# Sheet1.net
KiCad netlist of a schematic drawn in Altium Designer
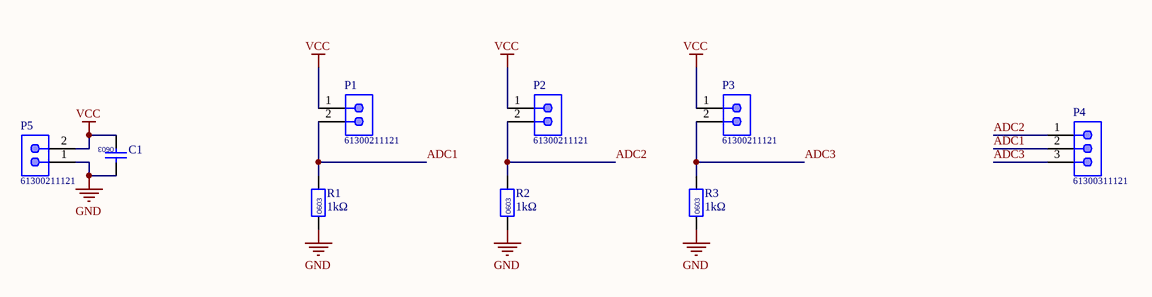
[diagram p0: Sheet1.SchDoc]

(export (version "E")
  (design (tool "Eeschema 10.0.6"))
  (components
    (comp (ref "C1")
      (value "~")
      (footprint "C_0603")
      (description "MLCC - SMD/SMT Capacitor 50V")
      (fields (field (name "VOLTAGE") "50V"))
      (libsource (lib "2021-1") (part "Capacitor_0603"))
    )
    (comp (ref "P1")
      (value "61300211121")
      (footprint "61300211121")
      (description "WR-PHD Pin Header, THT, pitch 2.54mm, Single Row, Vertical, 2p")
      (fields (field (name "MANUFACTURER") "Wurth Elektronik"))
      (libsource (lib "Gold_Pin_WE_2_54(rev20a)") (part "61300211121"))
    )
    (comp (ref "P2")
      (value "61300211121")
      (footprint "61300211121")
      (description "WR-PHD Pin Header, THT, pitch 2.54mm, Single Row, Vertical, 2p")
      (fields (field (name "MANUFACTURER") "Wurth Elektronik"))
      (libsource (lib "Gold_Pin_WE_2_54(rev20a)") (part "61300211121"))
    )
    (comp (ref "P3")
      (value "61300211121")
      (footprint "61300211121")
      (description "WR-PHD Pin Header, THT, pitch 2.54mm, Single Row, Vertical, 2p")
      (fields (field (name "MANUFACTURER") "Wurth Elektronik"))
      (libsource (lib "Gold_Pin_WE_2_54(rev20a)") (part "61300211121"))
    )
    (comp (ref "P4")
      (value "61300311121")
      (footprint "61300311121")
      (description "WR-PHD Pin Header, THT, pitch 2.54mm, Single Row, Vertical, 3p")
      (fields (field (name "MANUFACTURER") "Wurth Elektronik"))
      (libsource (lib "Gold_Pin_WE_2_54(rev20a)") (part "61300311121"))
    )
    (comp (ref "P5")
      (value "61300211121")
      (footprint "61300211121")
      (description "WR-PHD Pin Header, THT, pitch 2.54mm, Single Row, Vertical, 2p")
      (fields (field (name "MANUFACTURER") "Wurth Elektronik"))
      (libsource (lib "Gold_Pin_WE_2_54(rev20a)") (part "61300211121"))
    )
    (comp (ref "R1")
      (value "1kΩ")
      (footprint "R_0603")
      (description "SMT Resistor")
      (libsource (lib "2021-1") (part "Resistor_0603"))
    )
    (comp (ref "R2")
      (value "1kΩ")
      (footprint "R_0603")
      (description "SMT Resistor")
      (libsource (lib "2021-1") (part "Resistor_0603"))
    )
    (comp (ref "R3")
      (value "1kΩ")
      (footprint "R_0603")
      (description "SMT Resistor")
      (libsource (lib "2021-1") (part "Resistor_0603"))
    )
  )
  (nets
    (net (code "1") (name "/ADC1") (class "Default")
      (node (ref "P1") (pin "2") (pinfunction "2_2") (pintype "passive"))
      (node (ref "P4") (pin "2") (pinfunction "2_2") (pintype "passive"))
      (node (ref "R1") (pin "2") (pinfunction "2_2") (pintype "passive"))
    )
    (net (code "2") (name "/ADC2") (class "Default")
      (node (ref "P2") (pin "2") (pinfunction "2_2") (pintype "passive"))
      (node (ref "P4") (pin "1") (pinfunction "1_1") (pintype "passive"))
      (node (ref "R2") (pin "2") (pinfunction "2_2") (pintype "passive"))
    )
    (net (code "3") (name "/ADC3") (class "Default")
      (node (ref "P3") (pin "2") (pinfunction "2_2") (pintype "passive"))
      (node (ref "P4") (pin "3") (pinfunction "3_3") (pintype "passive"))
      (node (ref "R3") (pin "2") (pinfunction "2_2") (pintype "passive"))
    )
    (net (code "4") (name "GND") (class "Default")
      (node (ref "C1") (pin "2") (pinfunction "2_2") (pintype "passive"))
      (node (ref "P5") (pin "1") (pinfunction "1_1") (pintype "passive"))
      (node (ref "R1") (pin "1") (pinfunction "1_1") (pintype "passive"))
      (node (ref "R2") (pin "1") (pinfunction "1_1") (pintype "passive"))
      (node (ref "R3") (pin "1") (pinfunction "1_1") (pintype "passive"))
    )
    (net (code "5") (name "VCC") (class "Default")
      (node (ref "C1") (pin "1") (pinfunction "1_1") (pintype "passive"))
      (node (ref "P1") (pin "1") (pinfunction "1_1") (pintype "passive"))
      (node (ref "P2") (pin "1") (pinfunction "1_1") (pintype "passive"))
      (node (ref "P3") (pin "1") (pinfunction "1_1") (pintype "passive"))
      (node (ref "P5") (pin "2") (pinfunction "2_2") (pintype "passive"))
    )
  )
)
